# Board.net
KiCad netlist of a schematic drawn in EAGLE
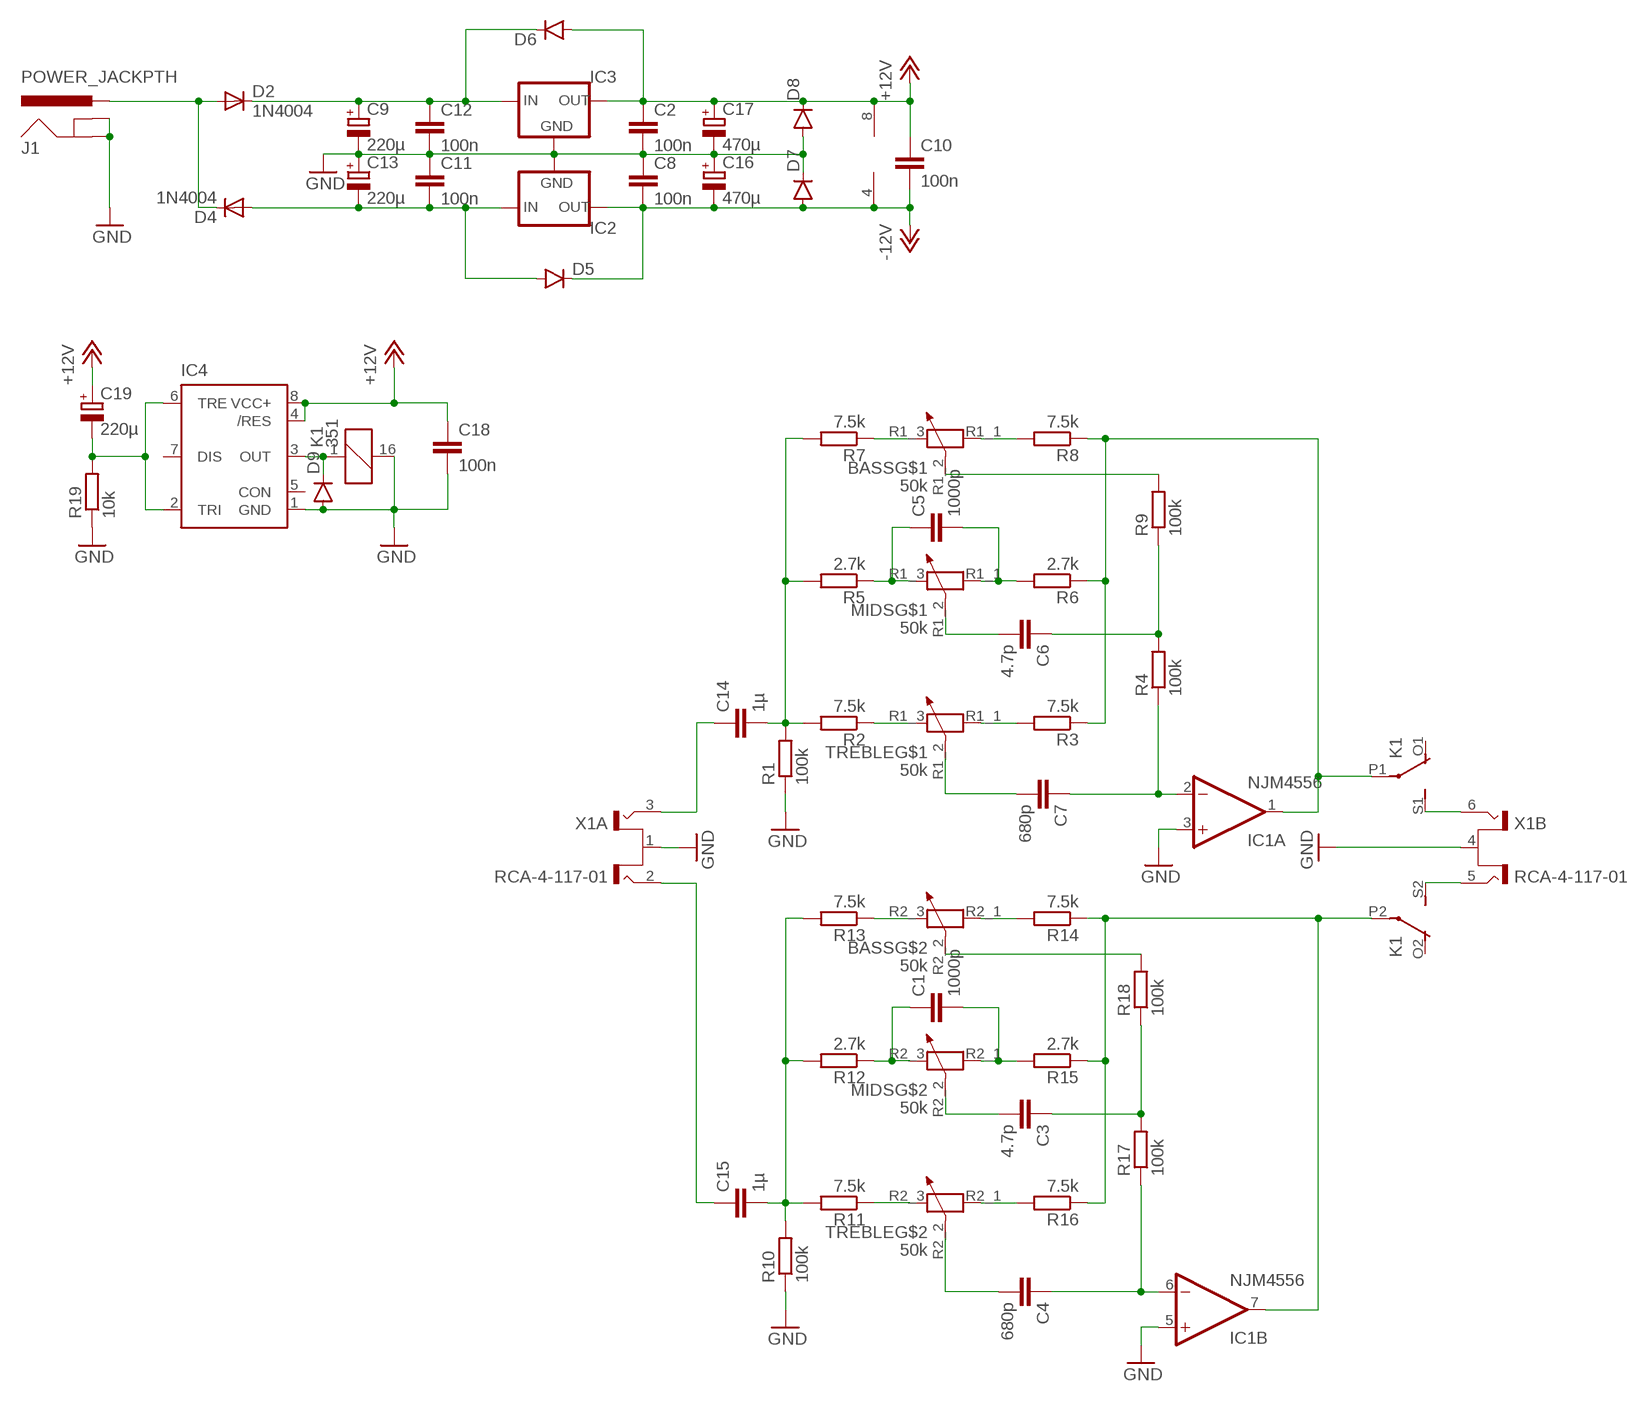
[diagram p0: schematic, sheet 1]

(export (version "E")
  (design (tool "Eeschema 10.0.6"))
  (components
    (comp (ref "BASS")
      (value "50k")
      (footprint "eagle-import:ALPS-RK09L12B0")
      (libsource (lib "eagle-import") (part "ALPS-RK09L12B0"))
    )
    (comp (ref "C1")
      (value "1000p")
      (footprint "eagle-import:C102-054X133")
      (libsource (lib "eagle-import") (part "C-EU102-054X133"))
    )
    (comp (ref "C2")
      (value "100n")
      (footprint "eagle-import:C0603")
      (libsource (lib "eagle-import") (part "C-EUC0603"))
    )
    (comp (ref "C3")
      (value "4.7p")
      (footprint "eagle-import:C050-045X075")
      (libsource (lib "eagle-import") (part "C-EU050-045X075"))
    )
    (comp (ref "C4")
      (value "680p")
      (footprint "eagle-import:C050-045X075")
      (libsource (lib "eagle-import") (part "C-EU050-045X075"))
    )
    (comp (ref "C5")
      (value "1000p")
      (footprint "eagle-import:C102-054X133")
      (libsource (lib "eagle-import") (part "C-EU102-054X133"))
    )
    (comp (ref "C6")
      (value "4.7p")
      (footprint "eagle-import:C050-045X075")
      (libsource (lib "eagle-import") (part "C-EU050-045X075"))
    )
    (comp (ref "C7")
      (value "680p")
      (footprint "eagle-import:C050-045X075")
      (libsource (lib "eagle-import") (part "C-EU050-045X075"))
    )
    (comp (ref "C8")
      (value "100n")
      (footprint "eagle-import:C0603")
      (libsource (lib "eagle-import") (part "C-EUC0603"))
    )
    (comp (ref "C9")
      (value "220µ")
      (footprint "eagle-import:175TMP-0810")
      (libsource (lib "eagle-import") (part "CPOL-EU175TMP-0810"))
    )
    (comp (ref "C10")
      (value "100n")
      (footprint "eagle-import:C0603")
      (libsource (lib "eagle-import") (part "C-EUC0603"))
    )
    (comp (ref "C11")
      (value "100n")
      (footprint "eagle-import:C0603")
      (libsource (lib "eagle-import") (part "C-EUC0603"))
    )
    (comp (ref "C12")
      (value "100n")
      (footprint "eagle-import:C0603")
      (libsource (lib "eagle-import") (part "C-EUC0603"))
    )
    (comp (ref "C13")
      (value "220µ")
      (footprint "eagle-import:175TMP-0810")
      (libsource (lib "eagle-import") (part "CPOL-EU175TMP-0810"))
    )
    (comp (ref "C14")
      (value "1µ")
      (footprint "eagle-import:C050-045X075")
      (libsource (lib "eagle-import") (part "C-EU050-045X075"))
    )
    (comp (ref "C15")
      (value "1µ")
      (footprint "eagle-import:C050-045X075")
      (libsource (lib "eagle-import") (part "C-EU050-045X075"))
    )
    (comp (ref "C16")
      (value "470µ")
      (footprint "eagle-import:175TMP-0810")
      (libsource (lib "eagle-import") (part "CPOL-EU175TMP-0810"))
    )
    (comp (ref "C17")
      (value "470µ")
      (footprint "eagle-import:175TMP-0810")
      (libsource (lib "eagle-import") (part "CPOL-EU175TMP-0810"))
    )
    (comp (ref "C18")
      (value "100n")
      (footprint "eagle-import:C0603")
      (libsource (lib "eagle-import") (part "C-EUC0603"))
    )
    (comp (ref "C19")
      (value "220µ")
      (footprint "eagle-import:175TMP-0810")
      (libsource (lib "eagle-import") (part "CPOL-EU175TMP-0810"))
    )
    (comp (ref "D2")
      (value "1N4004")
      (footprint "eagle-import:DO41-10")
      (libsource (lib "eagle-import") (part "1N4004"))
    )
    (comp (ref "D4")
      (value "1N4004")
      (footprint "eagle-import:DO41-10")
      (libsource (lib "eagle-import") (part "1N4004"))
    )
    (comp (ref "D5")
      (value "DIODEBAS16")
      (footprint "eagle-import:SOD-323")
      (libsource (lib "eagle-import") (part "DIODEBAS16"))
    )
    (comp (ref "D6")
      (value "DIODEBAS16")
      (footprint "eagle-import:SOD-323")
      (libsource (lib "eagle-import") (part "DIODEBAS16"))
    )
    (comp (ref "D7")
      (value "DIODEBAS16")
      (footprint "eagle-import:SOD-323")
      (libsource (lib "eagle-import") (part "DIODEBAS16"))
    )
    (comp (ref "D8")
      (value "DIODEBAS16")
      (footprint "eagle-import:SOD-323")
      (libsource (lib "eagle-import") (part "DIODEBAS16"))
    )
    (comp (ref "D9")
      (value "DIODEBAS16")
      (footprint "eagle-import:SOD-323")
      (libsource (lib "eagle-import") (part "DIODEBAS16"))
    )
    (comp (ref "IC1")
      (value "NJM4556")
      (footprint "eagle-import:DIL08")
      (libsource (lib "eagle-import") (part "LM358N"))
    )
    (comp (ref "IC2")
      (value "79XXS")
      (footprint "eagle-import:79XXS")
      (libsource (lib "eagle-import") (part "79XXS"))
    )
    (comp (ref "IC3")
      (value "78XXS")
      (footprint "eagle-import:78XXS")
      (libsource (lib "eagle-import") (part "78XXS"))
    )
    (comp (ref "IC4")
      (value "NE555D")
      (footprint "eagle-import:SO08")
      (libsource (lib "eagle-import") (part "NE555D"))
    )
    (comp (ref "J1")
      (value "POWER_JACKPTH")
      (footprint "eagle-import:POWER_JACK_PTH")
      (libsource (lib "eagle-import") (part "POWER_JACKPTH"))
    )
    (comp (ref "K1")
      (value "351")
      (footprint "eagle-import:351")
      (libsource (lib "eagle-import") (part "351"))
    )
    (comp (ref "MIDS")
      (value "50k")
      (footprint "eagle-import:ALPS-RK09L12B0")
      (libsource (lib "eagle-import") (part "OwnStuff_2060095_ALPS-RK09L12B0"))
    )
    (comp (ref "R1")
      (value "100k")
      (footprint "eagle-import:R1206")
      (libsource (lib "eagle-import") (part "R-EU_R1206"))
    )
    (comp (ref "R2")
      (value "7.5k")
      (footprint "eagle-import:R1206")
      (libsource (lib "eagle-import") (part "R-EU_R1206"))
    )
    (comp (ref "R3")
      (value "7.5k")
      (footprint "eagle-import:R1206")
      (libsource (lib "eagle-import") (part "R-EU_R1206"))
    )
    (comp (ref "R4")
      (value "100k")
      (footprint "eagle-import:R1206")
      (libsource (lib "eagle-import") (part "R-EU_R1206"))
    )
    (comp (ref "R5")
      (value "2.7k")
      (footprint "eagle-import:R1206")
      (libsource (lib "eagle-import") (part "R-EU_R1206"))
    )
    (comp (ref "R6")
      (value "2.7k")
      (footprint "eagle-import:R1206")
      (libsource (lib "eagle-import") (part "R-EU_R1206"))
    )
    (comp (ref "R7")
      (value "7.5k")
      (footprint "eagle-import:R1206")
      (libsource (lib "eagle-import") (part "R-EU_R1206"))
    )
    (comp (ref "R8")
      (value "7.5k")
      (footprint "eagle-import:R1206")
      (libsource (lib "eagle-import") (part "R-EU_R1206"))
    )
    (comp (ref "R9")
      (value "100k")
      (footprint "eagle-import:R1206")
      (libsource (lib "eagle-import") (part "R-EU_R1206"))
    )
    (comp (ref "R10")
      (value "100k")
      (footprint "eagle-import:R1206")
      (libsource (lib "eagle-import") (part "R-EU_R1206"))
    )
    (comp (ref "R11")
      (value "7.5k")
      (footprint "eagle-import:R1206")
      (libsource (lib "eagle-import") (part "R-EU_R1206"))
    )
    (comp (ref "R12")
      (value "2.7k")
      (footprint "eagle-import:R1206")
      (libsource (lib "eagle-import") (part "R-EU_R1206"))
    )
    (comp (ref "R13")
      (value "7.5k")
      (footprint "eagle-import:R1206")
      (libsource (lib "eagle-import") (part "R-EU_R1206"))
    )
    (comp (ref "R14")
      (value "7.5k")
      (footprint "eagle-import:R1206")
      (libsource (lib "eagle-import") (part "R-EU_R1206"))
    )
    (comp (ref "R15")
      (value "2.7k")
      (footprint "eagle-import:R1206")
      (libsource (lib "eagle-import") (part "R-EU_R1206"))
    )
    (comp (ref "R16")
      (value "7.5k")
      (footprint "eagle-import:R1206")
      (libsource (lib "eagle-import") (part "R-EU_R1206"))
    )
    (comp (ref "R17")
      (value "100k")
      (footprint "eagle-import:R1206")
      (libsource (lib "eagle-import") (part "R-EU_R1206"))
    )
    (comp (ref "R18")
      (value "100k")
      (footprint "eagle-import:R1206")
      (libsource (lib "eagle-import") (part "R-EU_R1206"))
    )
    (comp (ref "R19")
      (value "10k")
      (footprint "eagle-import:R1206")
      (libsource (lib "eagle-import") (part "R-EU_R1206"))
    )
    (comp (ref "TREBLE")
      (value "50k")
      (footprint "eagle-import:ALPS-RK09L12B0")
      (libsource (lib "eagle-import") (part "OwnStuff_2060095_ALPS-RK09L12B0"))
    )
    (comp (ref "X1")
      (value "RCA-4-117-01")
      (footprint "eagle-import:RCA-4-117-01")
      (fields (field (name "SPICEPREFIX") "M"))
      (libsource (lib "eagle-import") (part "RCA-4-117-01"))
    )
  )
  (nets
    (net (code "1") (name "+12V") (class "Default")
      (node (ref "C10") (pin "1") (pinfunction "1_1") (pintype "passive"))
      (node (ref "C17") (pin "+") (pinfunction "+_+") (pintype "passive"))
      (node (ref "C18") (pin "1") (pinfunction "1_1") (pintype "passive"))
      (node (ref "C19") (pin "+") (pinfunction "+_+") (pintype "passive"))
      (node (ref "C2") (pin "1") (pinfunction "1_1") (pintype "passive"))
      (node (ref "D6") (pin "A") (pinfunction "A_A") (pintype "passive"))
      (node (ref "D8") (pin "C") (pinfunction "C_C") (pintype "passive"))
      (node (ref "IC1") (pin "8") (pinfunction "V+_8") (pintype "power_in"))
      (node (ref "IC3") (pin "OUT") (pinfunction "OUT_OUT") (pintype "passive"))
      (node (ref "IC4") (pin "4") (pinfunction "/RES_4") (pintype "input"))
      (node (ref "IC4") (pin "8") (pinfunction "VCC+_8") (pintype "power_in"))
    )
    (net (code "2") (name "-12V") (class "Default")
      (node (ref "C10") (pin "2") (pinfunction "2_2") (pintype "passive"))
      (node (ref "C16") (pin "-") (pinfunction "-_-") (pintype "passive"))
      (node (ref "C8") (pin "2") (pinfunction "2_2") (pintype "passive"))
      (node (ref "D5") (pin "C") (pinfunction "C_C") (pintype "passive"))
      (node (ref "D7") (pin "A") (pinfunction "A_A") (pintype "passive"))
      (node (ref "IC1") (pin "4") (pinfunction "V-_4") (pintype "power_in"))
      (node (ref "IC2") (pin "OUT") (pinfunction "OUT_OUT") (pintype "passive"))
    )
    (net (code "3") (name "GND") (class "Default")
      (node (ref "C11") (pin "1") (pinfunction "1_1") (pintype "passive"))
      (node (ref "C12") (pin "2") (pinfunction "2_2") (pintype "passive"))
      (node (ref "C13") (pin "+") (pinfunction "+_+") (pintype "passive"))
      (node (ref "C16") (pin "+") (pinfunction "+_+") (pintype "passive"))
      (node (ref "C17") (pin "-") (pinfunction "-_-") (pintype "passive"))
      (node (ref "C18") (pin "2") (pinfunction "2_2") (pintype "passive"))
      (node (ref "C2") (pin "2") (pinfunction "2_2") (pintype "passive"))
      (node (ref "C8") (pin "1") (pinfunction "1_1") (pintype "passive"))
      (node (ref "C9") (pin "-") (pinfunction "-_-") (pintype "passive"))
      (node (ref "D7") (pin "C") (pinfunction "C_C") (pintype "passive"))
      (node (ref "D8") (pin "A") (pinfunction "A_A") (pintype "passive"))
      (node (ref "D9") (pin "A") (pinfunction "A_A") (pintype "passive"))
      (node (ref "IC1") (pin "3") (pinfunction "+IN_3") (pintype "input"))
      (node (ref "IC1") (pin "5") (pinfunction "+IN_5") (pintype "input"))
      (node (ref "IC2") (pin "GND") (pinfunction "GND_GND") (pintype "input"))
      (node (ref "IC3") (pin "GND") (pinfunction "GND_GND") (pintype "input"))
      (node (ref "IC4") (pin "1") (pinfunction "GND_1") (pintype "power_in"))
      (node (ref "J1") (pin "GND") (pinfunction "GND_GND") (pintype "bidirectional"))
      (node (ref "J1") (pin "GNDBREAK") (pinfunction "GNDBREAK_GNDBREAK") (pintype "bidirectional"))
      (node (ref "K1") (pin "16") (pinfunction "2_16") (pintype "passive"))
      (node (ref "R1") (pin "1") (pinfunction "1_1") (pintype "passive"))
      (node (ref "R10") (pin "1") (pinfunction "1_1") (pintype "passive"))
      (node (ref "R19") (pin "1") (pinfunction "1_1") (pintype "passive"))
      (node (ref "X1") (pin "1") (pinfunction "S_1") (pintype "passive"))
      (node (ref "X1") (pin "4") (pinfunction "S_4") (pintype "passive"))
    )
    (net (code "4") (name "Net-(BASSA-1)") (class "Default")
      (node (ref "BASS") (pin "R1_1") (pinfunction "1_R1_1") (pintype "passive"))
      (node (ref "R8") (pin "2") (pinfunction "2_2") (pintype "passive"))
    )
    (net (code "5") (name "Net-(BASSA-2)") (class "Default")
      (node (ref "BASS") (pin "R1_3") (pinfunction "2_R1_3") (pintype "passive"))
      (node (ref "R7") (pin "1") (pinfunction "1_1") (pintype "passive"))
    )
    (net (code "6") (name "Net-(BASSA-3)") (class "Default")
      (node (ref "BASS") (pin "R1_2") (pinfunction "3_R1_2") (pintype "passive"))
      (node (ref "R9") (pin "2") (pinfunction "2_2") (pintype "passive"))
    )
    (net (code "7") (name "Net-(BASSB-1)") (class "Default")
      (node (ref "BASS") (pin "R2_1") (pinfunction "1_R2_1") (pintype "passive"))
      (node (ref "R14") (pin "2") (pinfunction "2_2") (pintype "passive"))
    )
    (net (code "8") (name "Net-(BASSB-2)") (class "Default")
      (node (ref "BASS") (pin "R2_3") (pinfunction "2_R2_3") (pintype "passive"))
      (node (ref "R13") (pin "1") (pinfunction "1_1") (pintype "passive"))
    )
    (net (code "9") (name "Net-(BASSB-3)") (class "Default")
      (node (ref "BASS") (pin "R2_2") (pinfunction "3_R2_2") (pintype "passive"))
      (node (ref "R18") (pin "2") (pinfunction "2_2") (pintype "passive"))
    )
    (net (code "10") (name "Net-(C3-Pad1)") (class "Default")
      (node (ref "C3") (pin "1") (pinfunction "1_1") (pintype "passive"))
      (node (ref "R17") (pin "2") (pinfunction "2_2") (pintype "passive"))
      (node (ref "R18") (pin "1") (pinfunction "1_1") (pintype "passive"))
    )
    (net (code "11") (name "Net-(C6-Pad1)") (class "Default")
      (node (ref "C6") (pin "1") (pinfunction "1_1") (pintype "passive"))
      (node (ref "R4") (pin "2") (pinfunction "2_2") (pintype "passive"))
      (node (ref "R9") (pin "1") (pinfunction "1_1") (pintype "passive"))
    )
    (net (code "12") (name "Net-(C11-Pad2)") (class "Default")
      (node (ref "C11") (pin "2") (pinfunction "2_2") (pintype "passive"))
      (node (ref "C13") (pin "-") (pinfunction "-_-") (pintype "passive"))
      (node (ref "D4") (pin "A") (pinfunction "A_A") (pintype "passive"))
      (node (ref "D5") (pin "A") (pinfunction "A_A") (pintype "passive"))
      (node (ref "IC2") (pin "IN") (pinfunction "IN_IN") (pintype "input"))
    )
    (net (code "13") (name "Net-(C12-Pad1)") (class "Default")
      (node (ref "C12") (pin "1") (pinfunction "1_1") (pintype "passive"))
      (node (ref "C9") (pin "+") (pinfunction "+_+") (pintype "passive"))
      (node (ref "D2") (pin "C") (pinfunction "C_C") (pintype "passive"))
      (node (ref "D6") (pin "C") (pinfunction "C_C") (pintype "passive"))
      (node (ref "IC3") (pin "IN") (pinfunction "IN_IN") (pintype "input"))
    )
    (net (code "14") (name "Net-(C14-Pad2)") (class "Default")
      (node (ref "C14") (pin "2") (pinfunction "2_2") (pintype "passive"))
      (node (ref "R1") (pin "2") (pinfunction "2_2") (pintype "passive"))
      (node (ref "R2") (pin "2") (pinfunction "2_2") (pintype "passive"))
      (node (ref "R5") (pin "2") (pinfunction "2_2") (pintype "passive"))
      (node (ref "R7") (pin "2") (pinfunction "2_2") (pintype "passive"))
    )
    (net (code "15") (name "Net-(C15-Pad2)") (class "Default")
      (node (ref "C15") (pin "2") (pinfunction "2_2") (pintype "passive"))
      (node (ref "R10") (pin "2") (pinfunction "2_2") (pintype "passive"))
      (node (ref "R11") (pin "2") (pinfunction "2_2") (pintype "passive"))
      (node (ref "R12") (pin "2") (pinfunction "2_2") (pintype "passive"))
      (node (ref "R13") (pin "2") (pinfunction "2_2") (pintype "passive"))
    )
    (net (code "16") (name "Net-(D2-PadA)") (class "Default")
      (node (ref "D2") (pin "A") (pinfunction "A_A") (pintype "passive"))
      (node (ref "D4") (pin "C") (pinfunction "C_C") (pintype "passive"))
      (node (ref "J1") (pin "PWR") (pinfunction "PWR_PWR") (pintype "bidirectional"))
    )
    (net (code "17") (name "Net-(IC1A--IN)") (class "Default")
      (node (ref "C7") (pin "1") (pinfunction "1_1") (pintype "passive"))
      (node (ref "IC1") (pin "2") (pinfunction "-IN_2") (pintype "input"))
      (node (ref "R4") (pin "1") (pinfunction "1_1") (pintype "passive"))
    )
    (net (code "18") (name "Net-(IC1A-OUT)") (class "Default")
      (node (ref "IC1") (pin "1") (pinfunction "OUT_1") (pintype "output"))
      (node (ref "K1") (pin "P1") (pinfunction "P_P1") (pintype "passive"))
      (node (ref "R3") (pin "1") (pinfunction "1_1") (pintype "passive"))
      (node (ref "R6") (pin "1") (pinfunction "1_1") (pintype "passive"))
      (node (ref "R8") (pin "1") (pinfunction "1_1") (pintype "passive"))
    )
    (net (code "19") (name "Net-(IC1B--IN)") (class "Default")
      (node (ref "C4") (pin "1") (pinfunction "1_1") (pintype "passive"))
      (node (ref "IC1") (pin "6") (pinfunction "-IN_6") (pintype "input"))
      (node (ref "R17") (pin "1") (pinfunction "1_1") (pintype "passive"))
    )
    (net (code "20") (name "Net-(IC1B-OUT)") (class "Default")
      (node (ref "IC1") (pin "7") (pinfunction "OUT_7") (pintype "output"))
      (node (ref "K1") (pin "P2") (pinfunction "P_P2") (pintype "passive"))
      (node (ref "R14") (pin "1") (pinfunction "1_1") (pintype "passive"))
      (node (ref "R15") (pin "1") (pinfunction "1_1") (pintype "passive"))
      (node (ref "R16") (pin "1") (pinfunction "1_1") (pintype "passive"))
    )
    (net (code "21") (name "Net-(IC4-OUT)") (class "Default")
      (node (ref "D9") (pin "C") (pinfunction "C_C") (pintype "passive"))
      (node (ref "IC4") (pin "3") (pinfunction "OUT_3") (pintype "output"))
      (node (ref "K1") (pin "1") (pinfunction "1_1") (pintype "passive"))
    )
    (net (code "22") (name "Net-(IC4-TRE)") (class "Default")
      (node (ref "C19") (pin "-") (pinfunction "-_-") (pintype "passive"))
      (node (ref "IC4") (pin "2") (pinfunction "TRI_2") (pintype "input"))
      (node (ref "IC4") (pin "6") (pinfunction "TRE_6") (pintype "input"))
      (node (ref "R19") (pin "2") (pinfunction "2_2") (pintype "passive"))
    )
    (net (code "23") (name "Net-(K1B-S)") (class "Default")
      (node (ref "K1") (pin "S1") (pinfunction "S_S1") (pintype "passive"))
      (node (ref "X1") (pin "6") (pinfunction "T2_6") (pintype "passive"))
    )
    (net (code "24") (name "Net-(K1C-S)") (class "Default")
      (node (ref "K1") (pin "S2") (pinfunction "S_S2") (pintype "passive"))
      (node (ref "X1") (pin "5") (pinfunction "T1_5") (pintype "passive"))
    )
    (net (code "25") (name "Net-(MIDSA-1)") (class "Default")
      (node (ref "C5") (pin "2") (pinfunction "2_2") (pintype "passive"))
      (node (ref "MIDS") (pin "R1_1") (pinfunction "1_R1_1") (pintype "passive"))
      (node (ref "R6") (pin "2") (pinfunction "2_2") (pintype "passive"))
    )
    (net (code "26") (name "Net-(MIDSA-2)") (class "Default")
      (node (ref "C5") (pin "1") (pinfunction "1_1") (pintype "passive"))
      (node (ref "MIDS") (pin "R1_3") (pinfunction "2_R1_3") (pintype "passive"))
      (node (ref "R5") (pin "1") (pinfunction "1_1") (pintype "passive"))
    )
    (net (code "27") (name "Net-(MIDSA-3)") (class "Default")
      (node (ref "C6") (pin "2") (pinfunction "2_2") (pintype "passive"))
      (node (ref "MIDS") (pin "R1_2") (pinfunction "3_R1_2") (pintype "passive"))
    )
    (net (code "28") (name "Net-(MIDSB-1)") (class "Default")
      (node (ref "C1") (pin "2") (pinfunction "2_2") (pintype "passive"))
      (node (ref "MIDS") (pin "R2_1") (pinfunction "1_R2_1") (pintype "passive"))
      (node (ref "R15") (pin "2") (pinfunction "2_2") (pintype "passive"))
    )
    (net (code "29") (name "Net-(MIDSB-2)") (class "Default")
      (node (ref "C1") (pin "1") (pinfunction "1_1") (pintype "passive"))
      (node (ref "MIDS") (pin "R2_3") (pinfunction "2_R2_3") (pintype "passive"))
      (node (ref "R12") (pin "1") (pinfunction "1_1") (pintype "passive"))
    )
    (net (code "30") (name "Net-(MIDSB-3)") (class "Default")
      (node (ref "C3") (pin "2") (pinfunction "2_2") (pintype "passive"))
      (node (ref "MIDS") (pin "R2_2") (pinfunction "3_R2_2") (pintype "passive"))
    )
    (net (code "31") (name "Net-(TREBLEA-1)") (class "Default")
      (node (ref "R3") (pin "2") (pinfunction "2_2") (pintype "passive"))
      (node (ref "TREBLE") (pin "R1_1") (pinfunction "1_R1_1") (pintype "passive"))
    )
    (net (code "32") (name "Net-(TREBLEA-2)") (class "Default")
      (node (ref "R2") (pin "1") (pinfunction "1_1") (pintype "passive"))
      (node (ref "TREBLE") (pin "R1_3") (pinfunction "2_R1_3") (pintype "passive"))
    )
    (net (code "33") (name "Net-(TREBLEA-3)") (class "Default")
      (node (ref "C7") (pin "2") (pinfunction "2_2") (pintype "passive"))
      (node (ref "TREBLE") (pin "R1_2") (pinfunction "3_R1_2") (pintype "passive"))
    )
    (net (code "34") (name "Net-(TREBLEB-1)") (class "Default")
      (node (ref "R16") (pin "2") (pinfunction "2_2") (pintype "passive"))
      (node (ref "TREBLE") (pin "R2_1") (pinfunction "1_R2_1") (pintype "passive"))
    )
    (net (code "35") (name "Net-(TREBLEB-2)") (class "Default")
      (node (ref "R11") (pin "1") (pinfunction "1_1") (pintype "passive"))
      (node (ref "TREBLE") (pin "R2_3") (pinfunction "2_R2_3") (pintype "passive"))
    )
    (net (code "36") (name "Net-(TREBLEB-3)") (class "Default")
      (node (ref "C4") (pin "2") (pinfunction "2_2") (pintype "passive"))
      (node (ref "TREBLE") (pin "R2_2") (pinfunction "3_R2_2") (pintype "passive"))
    )
    (net (code "37") (name "Net-(X1A-T1)") (class "Default")
      (node (ref "C15") (pin "1") (pinfunction "1_1") (pintype "passive"))
      (node (ref "X1") (pin "2") (pinfunction "T1_2") (pintype "passive"))
    )
    (net (code "38") (name "Net-(X1A-T2)") (class "Default")
      (node (ref "C14") (pin "1") (pinfunction "1_1") (pintype "passive"))
      (node (ref "X1") (pin "3") (pinfunction "T2_3") (pintype "passive"))
    )
    (net (code "39") (name "unconnected-(IC4-CON-Pad5)") (class "Default")
      (node (ref "IC4") (pin "5") (pinfunction "CON_5") (pintype "input"))
    )
    (net (code "40") (name "unconnected-(IC4-DIS-Pad7)") (class "Default")
      (node (ref "IC4") (pin "7") (pinfunction "DIS_7") (pintype "input"))
    )
    (net (code "41") (name "unconnected-(K1B-O-PadO1)") (class "Default")
      (node (ref "K1") (pin "O1") (pinfunction "O_O1") (pintype "passive"))
    )
    (net (code "42") (name "unconnected-(K1C-O-PadO2)") (class "Default")
      (node (ref "K1") (pin "O2") (pinfunction "O_O2") (pintype "passive"))
    )
  )
)
